# Main_Board.net
KiCad netlist of a schematic drawn in Altium Designer
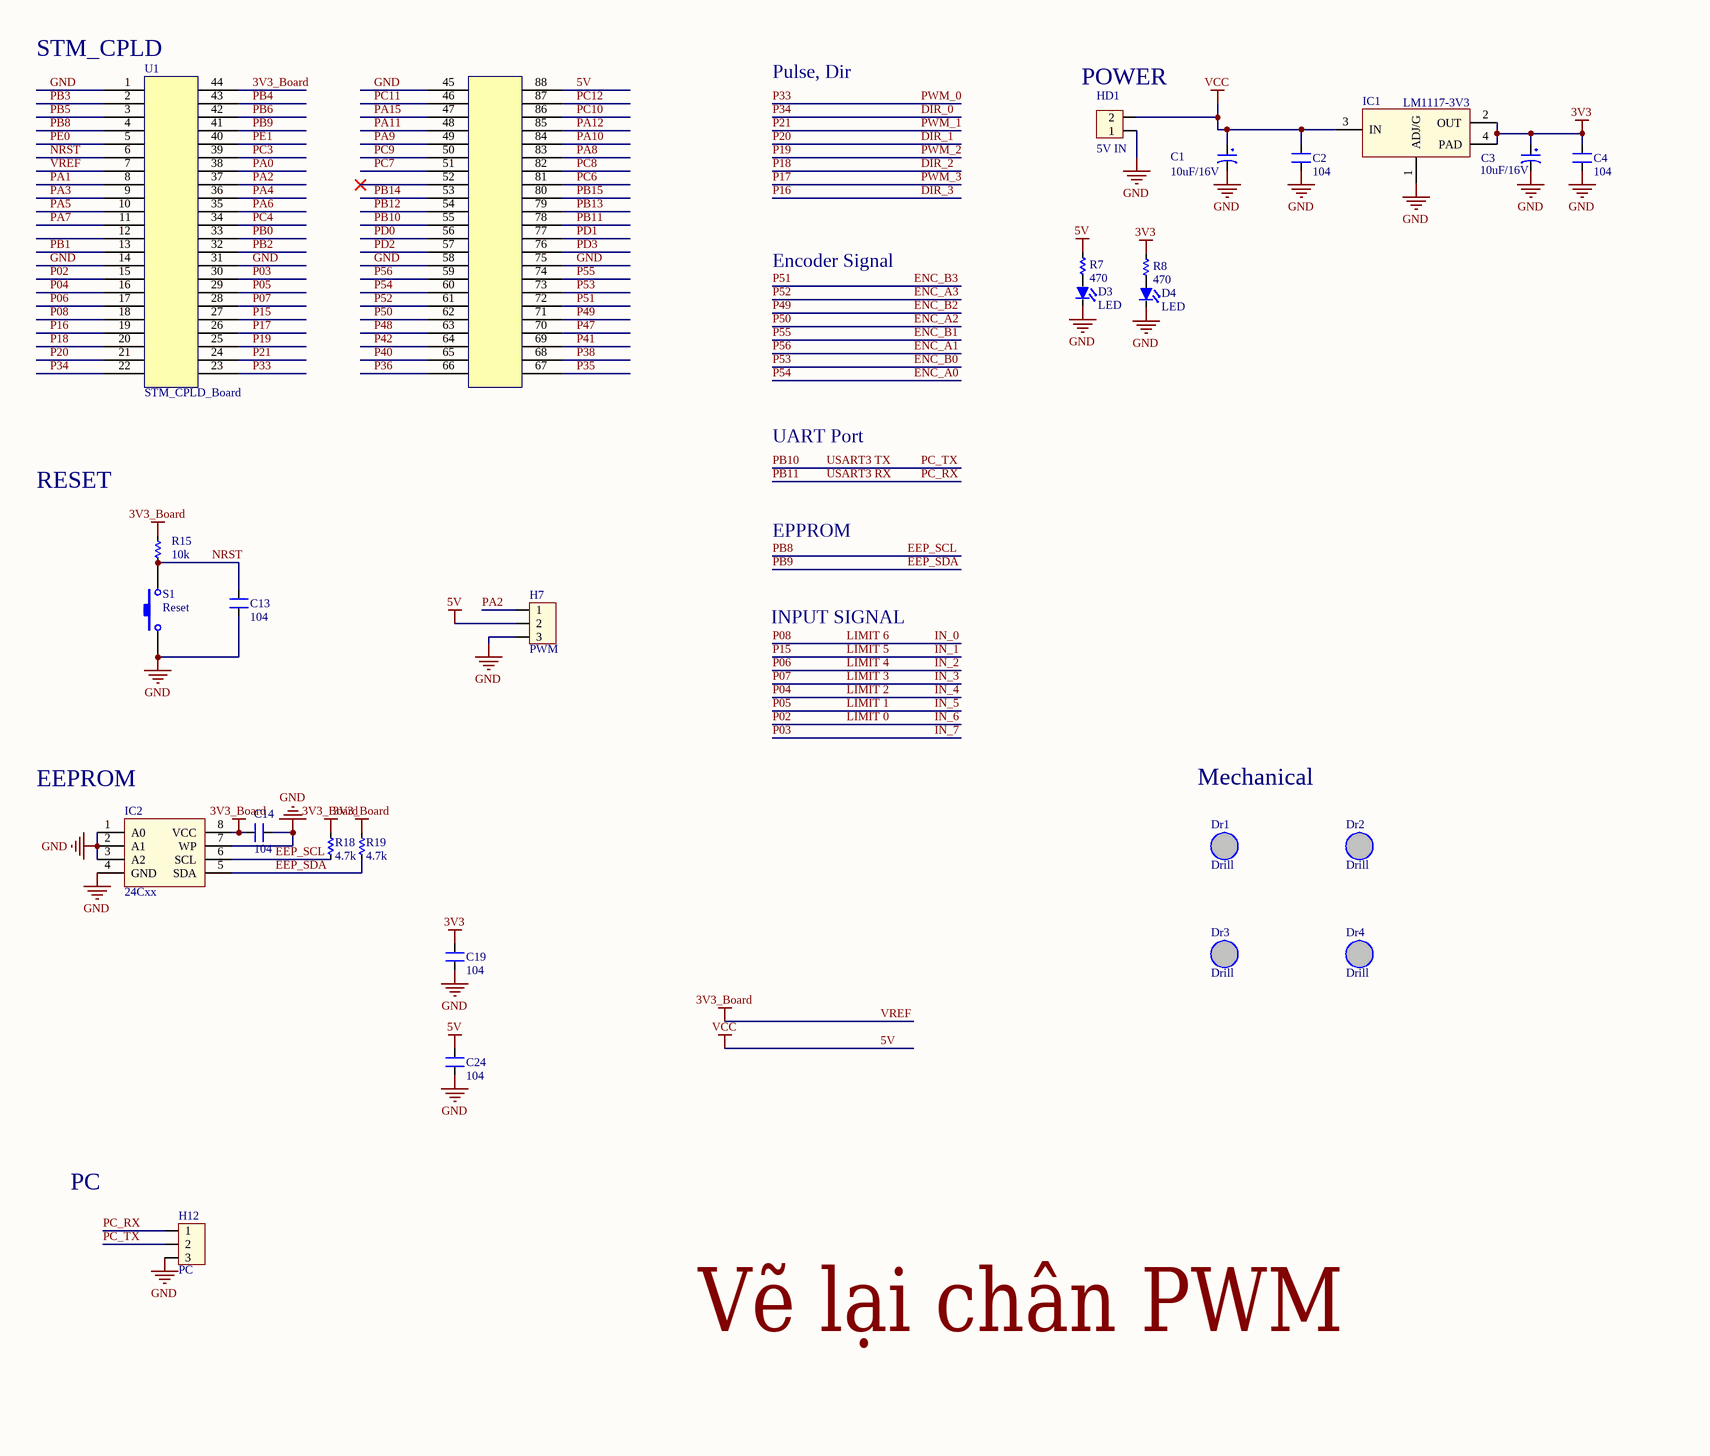
[diagram p0: Main_Board.SchDoc, top left]
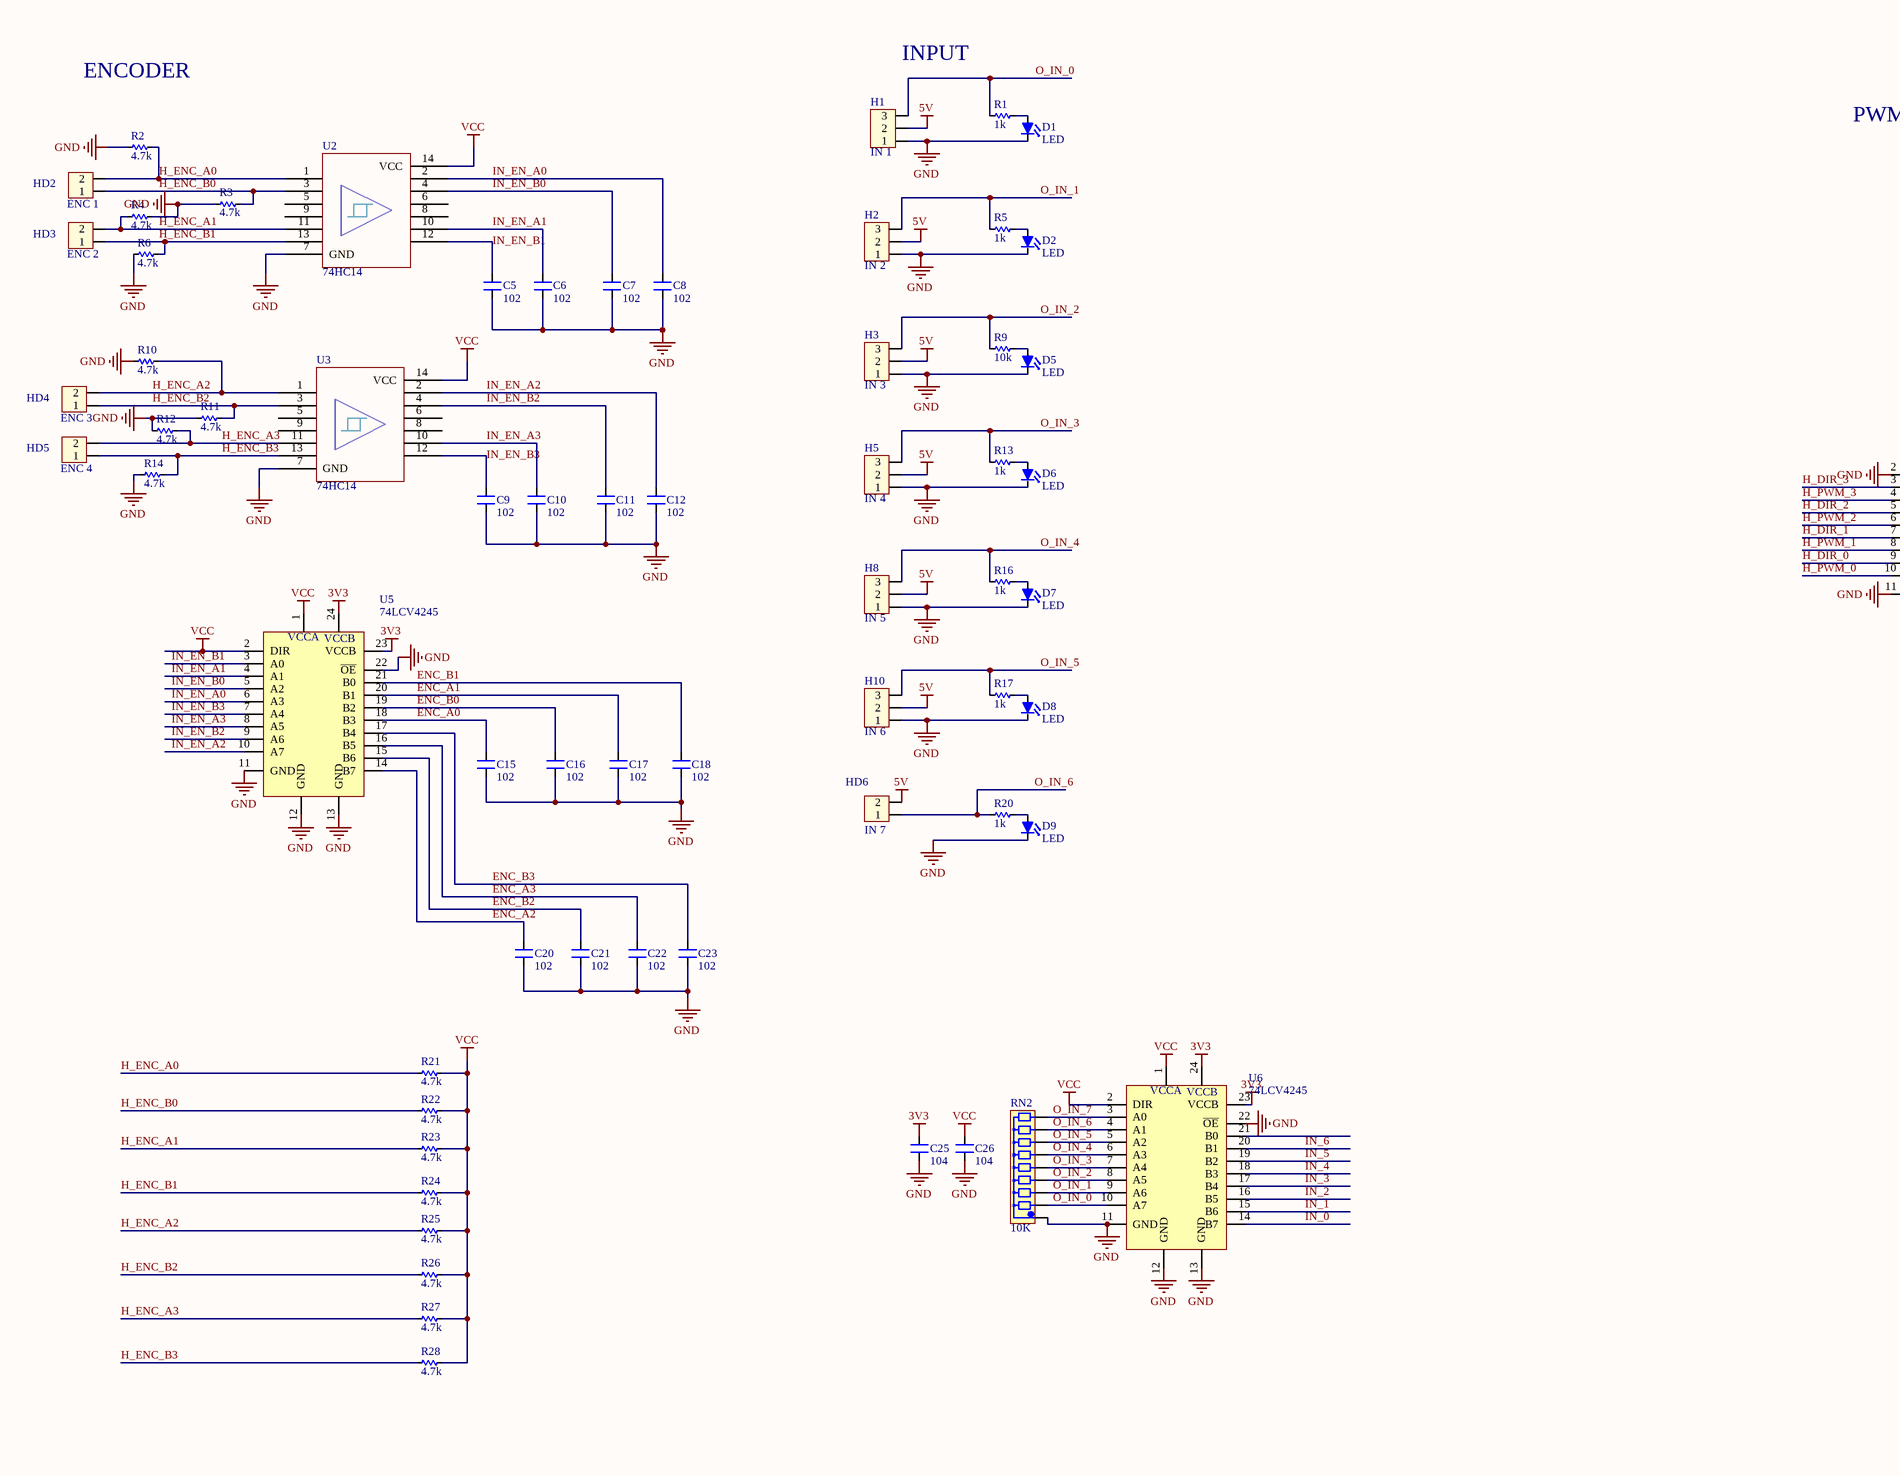
[diagram p1: Main_Board.SchDoc, top middle]
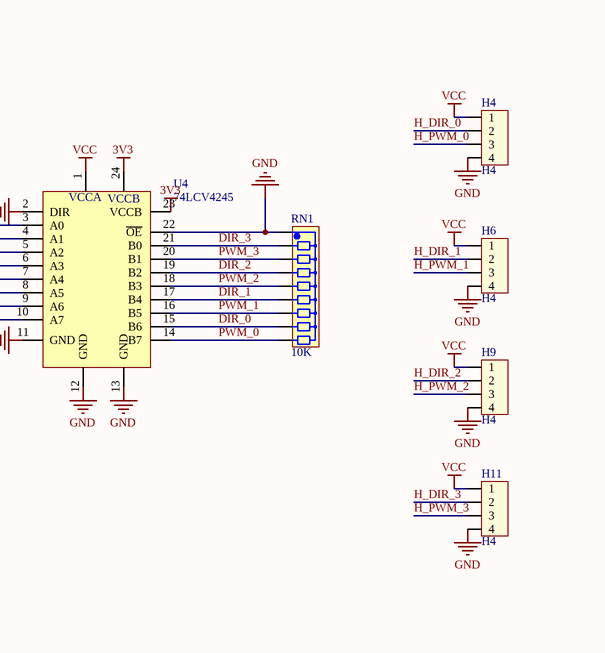
[diagram p2: Main_Board.SchDoc, top right]
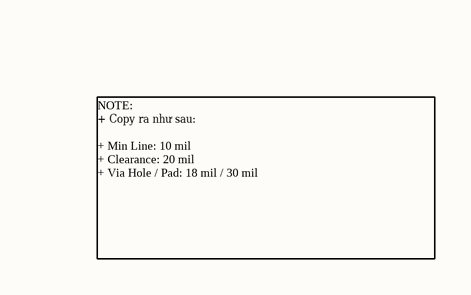
[diagram p3: Main_Board.SchDoc, bottom right]

(export (version "E")
  (design (tool "Eeschema 10.0.6"))
  (components
    (comp (ref "C1")
      (value "10uF/16V")
      (footprint "CAP_ALU_B")
      (description "C 47uF/50V , 220uF/16V")
      (libsource (lib "Main_Board") (part "CP2"))
    )
    (comp (ref "C2")
      (value "104")
      (footprint "CAP-SM-0805")
      (description "Ceramic Capacitor SMD")
      (libsource (lib "Main_Board") (part "CAP_SM_0805"))
    )
    (comp (ref "C3")
      (value "10uF/16V")
      (footprint "CAP_ALU_B")
      (description "C 47uF/50V , 220uF/16V")
      (libsource (lib "Main_Board") (part "CP2"))
    )
    (comp (ref "C4")
      (value "104")
      (footprint "CAP-SM-0805")
      (description "Ceramic Capacitor SMD")
      (libsource (lib "Main_Board") (part "CAP_SM_0805"))
    )
    (comp (ref "C5")
      (value "102")
      (footprint "CAP-SM-0805")
      (description "Ceramic Capacitor SMD")
      (libsource (lib "Main_Board") (part "CAP_SM_0805"))
    )
    (comp (ref "C6")
      (value "102")
      (footprint "CAP-SM-0805")
      (description "Ceramic Capacitor SMD")
      (libsource (lib "Main_Board") (part "CAP_SM_0805"))
    )
    (comp (ref "C7")
      (value "102")
      (footprint "CAP-SM-0805")
      (description "Ceramic Capacitor SMD")
      (libsource (lib "Main_Board") (part "CAP_SM_0805"))
    )
    (comp (ref "C8")
      (value "102")
      (footprint "CAP-SM-0805")
      (description "Ceramic Capacitor SMD")
      (libsource (lib "Main_Board") (part "CAP_SM_0805"))
    )
    (comp (ref "C9")
      (value "102")
      (footprint "CAP-SM-0805")
      (description "Ceramic Capacitor SMD")
      (libsource (lib "Main_Board") (part "CAP_SM_0805"))
    )
    (comp (ref "C10")
      (value "102")
      (footprint "CAP-SM-0805")
      (description "Ceramic Capacitor SMD")
      (libsource (lib "Main_Board") (part "CAP_SM_0805"))
    )
    (comp (ref "C11")
      (value "102")
      (footprint "CAP-SM-0805")
      (description "Ceramic Capacitor SMD")
      (libsource (lib "Main_Board") (part "CAP_SM_0805"))
    )
    (comp (ref "C12")
      (value "102")
      (footprint "CAP-SM-0805")
      (description "Ceramic Capacitor SMD")
      (libsource (lib "Main_Board") (part "CAP_SM_0805"))
    )
    (comp (ref "C13")
      (value "104")
      (footprint "CAP-SM-0805")
      (description "Ceramic Capacitor SMD")
      (libsource (lib "Main_Board") (part "CAP_SM_0805"))
    )
    (comp (ref "C14")
      (value "104")
      (footprint "CAP-SM-0805")
      (description "Ceramic Capacitor SMD")
      (libsource (lib "Main_Board") (part "CAP_SM_0805"))
    )
    (comp (ref "C15")
      (value "102")
      (footprint "CAP-SM-0805")
      (description "Ceramic Capacitor SMD")
      (libsource (lib "Main_Board") (part "CAP_SM_0805"))
    )
    (comp (ref "C16")
      (value "102")
      (footprint "CAP-SM-0805")
      (description "Ceramic Capacitor SMD")
      (libsource (lib "Main_Board") (part "CAP_SM_0805"))
    )
    (comp (ref "C17")
      (value "102")
      (footprint "CAP-SM-0805")
      (description "Ceramic Capacitor SMD")
      (libsource (lib "Main_Board") (part "CAP_SM_0805"))
    )
    (comp (ref "C18")
      (value "102")
      (footprint "CAP-SM-0805")
      (description "Ceramic Capacitor SMD")
      (libsource (lib "Main_Board") (part "CAP_SM_0805"))
    )
    (comp (ref "C19")
      (value "104")
      (footprint "CAP-SM-0805")
      (description "Ceramic Capacitor SMD")
      (libsource (lib "Main_Board") (part "CAP_SM_0805"))
    )
    (comp (ref "C20")
      (value "102")
      (footprint "CAP-SM-0805")
      (description "Ceramic Capacitor SMD")
      (libsource (lib "Main_Board") (part "CAP_SM_0805"))
    )
    (comp (ref "C21")
      (value "102")
      (footprint "CAP-SM-0805")
      (description "Ceramic Capacitor SMD")
      (libsource (lib "Main_Board") (part "CAP_SM_0805"))
    )
    (comp (ref "C22")
      (value "102")
      (footprint "CAP-SM-0805")
      (description "Ceramic Capacitor SMD")
      (libsource (lib "Main_Board") (part "CAP_SM_0805"))
    )
    (comp (ref "C23")
      (value "102")
      (footprint "CAP-SM-0805")
      (description "Ceramic Capacitor SMD")
      (libsource (lib "Main_Board") (part "CAP_SM_0805"))
    )
    (comp (ref "C24")
      (value "104")
      (footprint "CAP-SM-0805")
      (description "Ceramic Capacitor SMD")
      (libsource (lib "Main_Board") (part "CAP_SM_0805"))
    )
    (comp (ref "C25")
      (value "104")
      (footprint "CAP-SM-0805")
      (description "Ceramic Capacitor SMD")
      (libsource (lib "Main_Board") (part "CAP_SM_0805"))
    )
    (comp (ref "C26")
      (value "104")
      (footprint "CAP-SM-0805")
      (description "Ceramic Capacitor SMD")
      (libsource (lib "Main_Board") (part "CAP_SM_0805"))
    )
    (comp (ref "D1")
      (value "LED")
      (footprint "LED_0805_Blue")
      (description "LED SMD")
      (libsource (lib "Main_Board") (part "LED_SMD"))
    )
    (comp (ref "D2")
      (value "LED")
      (footprint "LED_0805_Blue")
      (description "LED SMD")
      (libsource (lib "Main_Board") (part "LED_SMD"))
    )
    (comp (ref "D3")
      (value "LED")
      (footprint "LED_0805_Blue")
      (description "LED SMD")
      (libsource (lib "Main_Board") (part "LED_SMD"))
    )
    (comp (ref "D4")
      (value "LED")
      (footprint "LED_0805_Blue")
      (description "LED SMD")
      (libsource (lib "Main_Board") (part "LED_SMD"))
    )
    (comp (ref "D5")
      (value "LED")
      (footprint "LED_0805_Blue")
      (description "LED SMD")
      (libsource (lib "Main_Board") (part "LED_SMD"))
    )
    (comp (ref "D6")
      (value "LED")
      (footprint "LED_0805_Blue")
      (description "LED SMD")
      (libsource (lib "Main_Board") (part "LED_SMD"))
    )
    (comp (ref "D7")
      (value "LED")
      (footprint "LED_0805_Blue")
      (description "LED SMD")
      (libsource (lib "Main_Board") (part "LED_SMD"))
    )
    (comp (ref "D8")
      (value "LED")
      (footprint "LED_0805_Blue")
      (description "LED SMD")
      (libsource (lib "Main_Board") (part "LED_SMD"))
    )
    (comp (ref "D9")
      (value "LED")
      (footprint "LED_0805_Blue")
      (description "LED SMD")
      (libsource (lib "Main_Board") (part "LED_SMD"))
    )
    (comp (ref "Dr1")
      (value "Drill")
      (footprint "Drill 3mm")
      (description "Drill 3mm")
      (libsource (lib "Main_Board") (part "Drill 3mm"))
    )
    (comp (ref "Dr2")
      (value "Drill")
      (footprint "Drill 3mm")
      (description "Drill 3mm")
      (libsource (lib "Main_Board") (part "Drill 3mm"))
    )
    (comp (ref "Dr3")
      (value "Drill")
      (footprint "Drill 3mm")
      (description "Drill 3mm")
      (libsource (lib "Main_Board") (part "Drill 3mm"))
    )
    (comp (ref "Dr4")
      (value "Drill")
      (footprint "Drill 3mm")
      (description "Drill 3mm")
      (libsource (lib "Main_Board") (part "Drill 3mm"))
    )
    (comp (ref "H1")
      (value "IN 1")
      (footprint "Header White 3")
      (description "Connector 3")
      (libsource (lib "") (part "Header white 3_1"))
    )
    (comp (ref "H2")
      (value "IN 2")
      (footprint "Header White 3")
      (description "Connector 3")
      (libsource (lib "") (part "Header white 3_1"))
    )
    (comp (ref "H3")
      (value "IN 3")
      (footprint "Header White 3")
      (description "Connector 3")
      (libsource (lib "") (part "Header white 3_1"))
    )
    (comp (ref "H4")
      (value "H4")
      (footprint "Header White 4")
      (description "Header white 4")
      (libsource (lib "Main_Board") (part "Header white 4"))
    )
    (comp (ref "H5")
      (value "IN 4")
      (footprint "Header White 3")
      (description "Connector 3")
      (libsource (lib "") (part "Header white 3_1"))
    )
    (comp (ref "H6")
      (value "H4")
      (footprint "Header White 4")
      (description "Header white 4")
      (libsource (lib "Main_Board") (part "Header white 4"))
    )
    (comp (ref "H7")
      (value "PWM")
      (footprint "Header White 3")
      (description "Connector 3")
      (libsource (lib "Main_Board") (part "Header white 3"))
    )
    (comp (ref "H8")
      (value "IN 5")
      (footprint "Header White 3")
      (description "Connector 3")
      (libsource (lib "") (part "Header white 3_1"))
    )
    (comp (ref "H9")
      (value "H4")
      (footprint "Header White 4")
      (description "Header white 4")
      (libsource (lib "Main_Board") (part "Header white 4"))
    )
    (comp (ref "H10")
      (value "IN 6")
      (footprint "Header White 3")
      (description "Connector 3")
      (libsource (lib "") (part "Header white 3_1"))
    )
    (comp (ref "H11")
      (value "H4")
      (footprint "Header White 4")
      (description "Header white 4")
      (libsource (lib "Main_Board") (part "Header white 4"))
    )
    (comp (ref "H12")
      (value "PC")
      (footprint "Header White 3")
      (description "Connector 3")
      (libsource (lib "Main_Board") (part "Header white 3"))
    )
    (comp (ref "HD1")
      (value "5V IN")
      (footprint "Domino 2")
      (description "Domino 2 200mil")
      (libsource (lib "Main_Board") (part "Domino 2"))
    )
    (comp (ref "HD2")
      (value "ENC 1")
      (footprint "Domino 2")
      (description "Domino 2 200mil")
      (libsource (lib "Main_Board") (part "Domino 2"))
    )
    (comp (ref "HD3")
      (value "ENC 2")
      (footprint "Domino 2")
      (description "Domino 2 200mil")
      (libsource (lib "Main_Board") (part "Domino 2"))
    )
    (comp (ref "HD4")
      (value "ENC 3")
      (footprint "Domino 2")
      (description "Domino 2 200mil")
      (libsource (lib "Main_Board") (part "Domino 2"))
    )
    (comp (ref "HD5")
      (value "ENC 4")
      (footprint "Domino 2")
      (description "Domino 2 200mil")
      (libsource (lib "Main_Board") (part "Domino 2"))
    )
    (comp (ref "HD6")
      (value "IN 7")
      (footprint "Domino 2")
      (description "Domino 2 200mil")
      (libsource (lib "Main_Board") (part "Domino 2"))
    )
    (comp (ref "IC1")
      (value "LM1117-3V3")
      (footprint "SOT223-4N")
      (description "Available in 1.8V, 2.5V, 2.85V, 3.3V, 5V, and  Adjustable Versions")
      (libsource (lib "Main_Board") (part "LM1117"))
    )
    (comp (ref "IC2")
      (value "24Cxx")
      (footprint "SOIC8")
      (description "Standard 2-Wire Bus Interface Serial EEPROM")
      (fields (field (name "COPYRIGHT BY") "VanDungEvn"))
      (libsource (lib "Main_Board") (part "24Cxx"))
    )
    (comp (ref "R1")
      (value "1k")
      (footprint "RES-SM-0805")
      (description "Resistor")
      (fields
        (field (name "MANUFACTURER") "Generic Components")
        (field (name "PUBLISHER") "Altium Hobart Technology Centre")
      )
      (libsource (lib "Main_Board") (part "Res-SMD"))
    )
    (comp (ref "R2")
      (value "4.7k")
      (footprint "RES-SM-0805")
      (description "Resistor")
      (fields
        (field (name "MANUFACTURER") "Generic Components")
        (field (name "PUBLISHER") "Altium Hobart Technology Centre")
      )
      (libsource (lib "Main_Board") (part "Res-SMD"))
    )
    (comp (ref "R3")
      (value "4.7k")
      (footprint "RES-SM-0805")
      (description "Resistor")
      (fields
        (field (name "MANUFACTURER") "Generic Components")
        (field (name "PUBLISHER") "Altium Hobart Technology Centre")
      )
      (libsource (lib "Main_Board") (part "Res-SMD"))
    )
    (comp (ref "R4")
      (value "4.7k")
      (footprint "RES-SM-0805")
      (description "Resistor")
      (fields
        (field (name "MANUFACTURER") "Generic Components")
        (field (name "PUBLISHER") "Altium Hobart Technology Centre")
      )
      (libsource (lib "Main_Board") (part "Res-SMD"))
    )
    (comp (ref "R5")
      (value "1k")
      (footprint "RES-SM-0805")
      (description "Resistor")
      (fields
        (field (name "MANUFACTURER") "Generic Components")
        (field (name "PUBLISHER") "Altium Hobart Technology Centre")
      )
      (libsource (lib "Main_Board") (part "Res-SMD"))
    )
    (comp (ref "R6")
      (value "4.7k")
      (footprint "RES-SM-0805")
      (description "Resistor")
      (fields
        (field (name "MANUFACTURER") "Generic Components")
        (field (name "PUBLISHER") "Altium Hobart Technology Centre")
      )
      (libsource (lib "Main_Board") (part "Res-SMD"))
    )
    (comp (ref "R7")
      (value "470")
      (footprint "RES-SM-0805")
      (description "Resistor")
      (fields
        (field (name "MANUFACTURER") "Generic Components")
        (field (name "PUBLISHER") "Altium Hobart Technology Centre")
      )
      (libsource (lib "Main_Board") (part "Res-SMD"))
    )
    (comp (ref "R8")
      (value "470")
      (footprint "RES-SM-0805")
      (description "Resistor")
      (fields
        (field (name "MANUFACTURER") "Generic Components")
        (field (name "PUBLISHER") "Altium Hobart Technology Centre")
      )
      (libsource (lib "Main_Board") (part "Res-SMD"))
    )
    (comp (ref "R9")
      (value "10k")
      (footprint "RES-SM-0805")
      (description "Resistor")
      (fields
        (field (name "MANUFACTURER") "Generic Components")
        (field (name "PUBLISHER") "Altium Hobart Technology Centre")
      )
      (libsource (lib "Main_Board") (part "Res-SMD"))
    )
    (comp (ref "R10")
      (value "4.7k")
      (footprint "RES-SM-0805")
      (description "Resistor")
      (fields
        (field (name "MANUFACTURER") "Generic Components")
        (field (name "PUBLISHER") "Altium Hobart Technology Centre")
      )
      (libsource (lib "Main_Board") (part "Res-SMD"))
    )
    (comp (ref "R11")
      (value "4.7k")
      (footprint "RES-SM-0805")
      (description "Resistor")
      (fields
        (field (name "MANUFACTURER") "Generic Components")
        (field (name "PUBLISHER") "Altium Hobart Technology Centre")
      )
      (libsource (lib "Main_Board") (part "Res-SMD"))
    )
    (comp (ref "R12")
      (value "4.7k")
      (footprint "RES-SM-0805")
      (description "Resistor")
      (fields
        (field (name "MANUFACTURER") "Generic Components")
        (field (name "PUBLISHER") "Altium Hobart Technology Centre")
      )
      (libsource (lib "Main_Board") (part "Res-SMD"))
    )
    (comp (ref "R13")
      (value "1k")
      (footprint "RES-SM-0805")
      (description "Resistor")
      (fields
        (field (name "MANUFACTURER") "Generic Components")
        (field (name "PUBLISHER") "Altium Hobart Technology Centre")
      )
      (libsource (lib "Main_Board") (part "Res-SMD"))
    )
    (comp (ref "R14")
      (value "4.7k")
      (footprint "RES-SM-0805")
      (description "Resistor")
      (fields
        (field (name "MANUFACTURER") "Generic Components")
        (field (name "PUBLISHER") "Altium Hobart Technology Centre")
      )
      (libsource (lib "Main_Board") (part "Res-SMD"))
    )
    (comp (ref "R15")
      (value "10k")
      (footprint "RES-SM-0805")
      (description "Resistor")
      (fields
        (field (name "MANUFACTURER") "Generic Components")
        (field (name "PUBLISHER") "Altium Hobart Technology Centre")
      )
      (libsource (lib "Main_Board") (part "Res-SMD"))
    )
    (comp (ref "R16")
      (value "1k")
      (footprint "RES-SM-0805")
      (description "Resistor")
      (fields
        (field (name "MANUFACTURER") "Generic Components")
        (field (name "PUBLISHER") "Altium Hobart Technology Centre")
      )
      (libsource (lib "Main_Board") (part "Res-SMD"))
    )
    (comp (ref "R17")
      (value "1k")
      (footprint "RES-SM-0805")
      (description "Resistor")
      (fields
        (field (name "MANUFACTURER") "Generic Components")
        (field (name "PUBLISHER") "Altium Hobart Technology Centre")
      )
      (libsource (lib "Main_Board") (part "Res-SMD"))
    )
    (comp (ref "R18")
      (value "4.7k")
      (footprint "RES-SM-0805")
      (description "Resistor")
      (fields
        (field (name "MANUFACTURER") "Generic Components")
        (field (name "PUBLISHER") "Altium Hobart Technology Centre")
      )
      (libsource (lib "Main_Board") (part "Res-SMD"))
    )
    (comp (ref "R19")
      (value "4.7k")
      (footprint "RES-SM-0805")
      (description "Resistor")
      (fields
        (field (name "MANUFACTURER") "Generic Components")
        (field (name "PUBLISHER") "Altium Hobart Technology Centre")
      )
      (libsource (lib "Main_Board") (part "Res-SMD"))
    )
    (comp (ref "R20")
      (value "1k")
      (footprint "RES-SM-0805")
      (description "Resistor")
      (fields
        (field (name "MANUFACTURER") "Generic Components")
        (field (name "PUBLISHER") "Altium Hobart Technology Centre")
      )
      (libsource (lib "Main_Board") (part "Res-SMD"))
    )
    (comp (ref "R21")
      (value "4.7k")
      (footprint "RES-SM-0805")
      (description "Resistor")
      (fields
        (field (name "MANUFACTURER") "Generic Components")
        (field (name "PUBLISHER") "Altium Hobart Technology Centre")
      )
      (libsource (lib "Main_Board") (part "Res-SMD"))
    )
    (comp (ref "R22")
      (value "4.7k")
      (footprint "RES-SM-0805")
      (description "Resistor")
      (fields
        (field (name "MANUFACTURER") "Generic Components")
        (field (name "PUBLISHER") "Altium Hobart Technology Centre")
      )
      (libsource (lib "Main_Board") (part "Res-SMD"))
    )
    (comp (ref "R23")
      (value "4.7k")
      (footprint "RES-SM-0805")
      (description "Resistor")
      (fields
        (field (name "MANUFACTURER") "Generic Components")
        (field (name "PUBLISHER") "Altium Hobart Technology Centre")
      )
      (libsource (lib "Main_Board") (part "Res-SMD"))
    )
    (comp (ref "R24")
      (value "4.7k")
      (footprint "RES-SM-0805")
      (description "Resistor")
      (fields
        (field (name "MANUFACTURER") "Generic Components")
        (field (name "PUBLISHER") "Altium Hobart Technology Centre")
      )
      (libsource (lib "Main_Board") (part "Res-SMD"))
    )
    (comp (ref "R25")
      (value "4.7k")
      (footprint "RES-SM-0805")
      (description "Resistor")
      (fields
        (field (name "MANUFACTURER") "Generic Components")
        (field (name "PUBLISHER") "Altium Hobart Technology Centre")
      )
      (libsource (lib "Main_Board") (part "Res-SMD"))
    )
    (comp (ref "R26")
      (value "4.7k")
      (footprint "RES-SM-0805")
      (description "Resistor")
      (fields
        (field (name "MANUFACTURER") "Generic Components")
        (field (name "PUBLISHER") "Altium Hobart Technology Centre")
      )
      (libsource (lib "Main_Board") (part "Res-SMD"))
    )
    (comp (ref "R27")
      (value "4.7k")
      (footprint "RES-SM-0805")
      (description "Resistor")
      (fields
        (field (name "MANUFACTURER") "Generic Components")
        (field (name "PUBLISHER") "Altium Hobart Technology Centre")
      )
      (libsource (lib "Main_Board") (part "Res-SMD"))
    )
    (comp (ref "R28")
      (value "4.7k")
      (footprint "RES-SM-0805")
      (description "Resistor")
      (fields
        (field (name "MANUFACTURER") "Generic Components")
        (field (name "PUBLISHER") "Altium Hobart Technology Centre")
      )
      (libsource (lib "Main_Board") (part "Res-SMD"))
    )
    (comp (ref "RN1")
      (value "10K")
      (footprint "RN8")
      (description "Resistor 8 (Thanh)")
      (libsource (lib "") (part "RN8_1"))
    )
    (comp (ref "RN2")
      (value "10K")
      (footprint "RN8")
      (description "Resistor 8 (Thanh)")
      (libsource (lib "Main_Board") (part "RN8"))
    )
    (comp (ref "S1")
      (value "Reset")
      (footprint "SW2")
      (description "Switch button 2 pin")
      (libsource (lib "Main_Board") (part "SW - 2Pin"))
    )
    (comp (ref "U1")
      (value "STM_CPLD_Board")
      (footprint "STM_CPLD_Board")
      (description "STM32f4 and Max2 570 on one board")
      (libsource (lib "Main_Board") (part "STM_CPLD_Board"))
    )
    (comp (ref "U2")
      (value "74HC14")
      (footprint "SO14-150mil")
      (description "Hex Inverters With SCHMITT-TRIGGER Inputs")
      (libsource (lib "Main_Board") (part "74HC14"))
    )
    (comp (ref "U3")
      (value "74HC14")
      (footprint "SO14-150mil")
      (description "Hex Inverters With SCHMITT-TRIGGER Inputs")
      (libsource (lib "Main_Board") (part "74HC14"))
    )
    (comp (ref "U4")
      (value "74LCV4245")
      (footprint "SOIC24 - wide")
      (description "Octal dual supply translating transceiver; 3-state")
      (libsource (lib "Main_Board") (part "74LCV4245"))
    )
    (comp (ref "U5")
      (value "74LCV4245")
      (footprint "SOIC24 - wide")
      (description "Octal dual supply translating transceiver; 3-state")
      (libsource (lib "Main_Board") (part "74LCV4245"))
    )
    (comp (ref "U6")
      (value "74LCV4245")
      (footprint "SOIC24 - wide")
      (description "Octal dual supply translating transceiver; 3-state")
      (libsource (lib "Main_Board") (part "74LCV4245"))
    )
  )
  (nets
    (net (code "1") (name "/DIR_0") (class "Default")
      (node (ref "RN1") (pin "8") (pinfunction "8_8") (pintype "passive"))
      (node (ref "U1") (pin "22") (pinfunction "22_22") (pintype "passive"))
      (node (ref "U4") (pin "15") (pinfunction "B6_15") (pintype "passive"))
    )
    (net (code "2") (name "/DIR_1") (class "Default")
      (node (ref "RN1") (pin "6") (pinfunction "6_6") (pintype "passive"))
      (node (ref "U1") (pin "21") (pinfunction "21_21") (pintype "passive"))
      (node (ref "U4") (pin "17") (pinfunction "B4_17") (pintype "passive"))
    )
    (net (code "3") (name "/DIR_2") (class "Default")
      (node (ref "RN1") (pin "4") (pinfunction "4_4") (pintype "passive"))
      (node (ref "U1") (pin "20") (pinfunction "20_20") (pintype "passive"))
      (node (ref "U4") (pin "19") (pinfunction "B2_19") (pintype "passive"))
    )
    (net (code "4") (name "/DIR_3") (class "Default")
      (node (ref "RN1") (pin "2") (pinfunction "2_2") (pintype "passive"))
      (node (ref "U1") (pin "19") (pinfunction "19_19") (pintype "passive"))
      (node (ref "U4") (pin "21") (pinfunction "B0_21") (pintype "passive"))
    )
    (net (code "5") (name "/EEP_SCL") (class "Default")
      (node (ref "IC2") (pin "6") (pinfunction "SCL_6") (pintype "passive"))
      (node (ref "R18") (pin "1") (pinfunction "1_1") (pintype "passive"))
      (node (ref "U1") (pin "4") (pinfunction "4_4") (pintype "passive"))
    )
    (net (code "6") (name "/EEP_SDA") (class "Default")
      (node (ref "IC2") (pin "5") (pinfunction "SDA_5") (pintype "passive"))
      (node (ref "R19") (pin "2") (pinfunction "2_2") (pintype "passive"))
      (node (ref "U1") (pin "41") (pinfunction "41_41") (pintype "passive"))
    )
    (net (code "7") (name "/ENC_A0") (class "Default")
      (node (ref "C15") (pin "2") (pinfunction "2_2") (pintype "passive"))
      (node (ref "U1") (pin "60") (pinfunction "60_60") (pintype "passive"))
      (node (ref "U5") (pin "18") (pinfunction "B3_18") (pintype "passive"))
    )
    (net (code "8") (name "/ENC_A1") (class "Default")
      (node (ref "C17") (pin "2") (pinfunction "2_2") (pintype "passive"))
      (node (ref "U1") (pin "59") (pinfunction "59_59") (pintype "passive"))
      (node (ref "U5") (pin "20") (pinfunction "B1_20") (pintype "passive"))
    )
    (net (code "9") (name "/ENC_A2") (class "Default")
      (node (ref "C20") (pin "2") (pinfunction "2_2") (pintype "passive"))
      (node (ref "U1") (pin "62") (pinfunction "62_62") (pintype "passive"))
      (node (ref "U5") (pin "14") (pinfunction "B7_14") (pintype "passive"))
    )
    (net (code "10") (name "/ENC_A3") (class "Default")
      (node (ref "C22") (pin "2") (pinfunction "2_2") (pintype "passive"))
      (node (ref "U1") (pin "61") (pinfunction "61_61") (pintype "passive"))
      (node (ref "U5") (pin "16") (pinfunction "B5_16") (pintype "passive"))
    )
    (net (code "11") (name "/ENC_B0") (class "Default")
      (node (ref "C16") (pin "2") (pinfunction "2_2") (pintype "passive"))
      (node (ref "U1") (pin "73") (pinfunction "73_73") (pintype "passive"))
      (node (ref "U5") (pin "19") (pinfunction "B2_19") (pintype "passive"))
    )
    (net (code "12") (name "/ENC_B1") (class "Default")
      (node (ref "C18") (pin "2") (pinfunction "2_2") (pintype "passive"))
      (node (ref "U1") (pin "74") (pinfunction "74_74") (pintype "passive"))
      (node (ref "U5") (pin "21") (pinfunction "B0_21") (pintype "passive"))
    )
    (net (code "13") (name "/ENC_B2") (class "Default")
      (node (ref "C21") (pin "2") (pinfunction "2_2") (pintype "passive"))
      (node (ref "U1") (pin "71") (pinfunction "71_71") (pintype "passive"))
      (node (ref "U5") (pin "15") (pinfunction "B6_15") (pintype "passive"))
    )
    (net (code "14") (name "/ENC_B3") (class "Default")
      (node (ref "C23") (pin "2") (pinfunction "2_2") (pintype "passive"))
      (node (ref "U1") (pin "72") (pinfunction "72_72") (pintype "passive"))
      (node (ref "U5") (pin "17") (pinfunction "B4_17") (pintype "passive"))
    )
    (net (code "15") (name "/H_DIR_0") (class "Default")
      (node (ref "H4") (pin "2") (pinfunction "2_2") (pintype "passive"))
      (node (ref "U4") (pin "9") (pinfunction "A6_9") (pintype "passive"))
    )
    (net (code "16") (name "/H_DIR_1") (class "Default")
      (node (ref "H6") (pin "2") (pinfunction "2_2") (pintype "passive"))
      (node (ref "U4") (pin "7") (pinfunction "A4_7") (pintype "passive"))
    )
    (net (code "17") (name "/H_DIR_2") (class "Default")
      (node (ref "H9") (pin "2") (pinfunction "2_2") (pintype "passive"))
      (node (ref "U4") (pin "5") (pinfunction "A2_5") (pintype "passive"))
    )
    (net (code "18") (name "/H_DIR_3") (class "Default")
      (node (ref "H11") (pin "2") (pinfunction "2_2") (pintype "passive"))
      (node (ref "U4") (pin "3") (pinfunction "A0_3") (pintype "passive"))
    )
    (net (code "19") (name "/H_ENC_A0") (class "Default")
      (node (ref "HD2") (pin "2") (pinfunction "2_2") (pintype "passive"))
      (node (ref "R2") (pin "1") (pinfunction "1_1") (pintype "passive"))
      (node (ref "R21") (pin "1") (pinfunction "1_1") (pintype "passive"))
      (node (ref "U2") (pin "1") (pintype "passive"))
    )
    (net (code "20") (name "/H_ENC_A1") (class "Default")
      (node (ref "HD3") (pin "2") (pinfunction "2_2") (pintype "passive"))
      (node (ref "R23") (pin "1") (pinfunction "1_1") (pintype "passive"))
      (node (ref "R4") (pin "2") (pinfunction "2_2") (pintype "passive"))
      (node (ref "U2") (pin "11") (pinfunction "10_11") (pintype "passive"))
    )
    (net (code "21") (name "/H_ENC_A2") (class "Default")
      (node (ref "HD4") (pin "2") (pinfunction "2_2") (pintype "passive"))
      (node (ref "R10") (pin "1") (pinfunction "1_1") (pintype "passive"))
      (node (ref "R25") (pin "1") (pinfunction "1_1") (pintype "passive"))
      (node (ref "U3") (pin "1") (pintype "passive"))
    )
    (net (code "22") (name "/H_ENC_A3") (class "Default")
      (node (ref "HD5") (pin "2") (pinfunction "2_2") (pintype "passive"))
      (node (ref "R12") (pin "1") (pinfunction "1_1") (pintype "passive"))
      (node (ref "R27") (pin "1") (pinfunction "1_1") (pintype "passive"))
      (node (ref "U3") (pin "11") (pinfunction "10_11") (pintype "passive"))
    )
    (net (code "23") (name "/H_ENC_B0") (class "Default")
      (node (ref "HD2") (pin "1") (pinfunction "1_1") (pintype "passive"))
      (node (ref "R22") (pin "1") (pinfunction "1_1") (pintype "passive"))
      (node (ref "R3") (pin "1") (pinfunction "1_1") (pintype "passive"))
      (node (ref "U2") (pin "3") (pintype "passive"))
    )
    (net (code "24") (name "/H_ENC_B1") (class "Default")
      (node (ref "HD3") (pin "1") (pinfunction "1_1") (pintype "passive"))
      (node (ref "R24") (pin "1") (pinfunction "1_1") (pintype "passive"))
      (node (ref "R6") (pin "1") (pinfunction "1_1") (pintype "passive"))
      (node (ref "U2") (pin "13") (pinfunction "12_13") (pintype "passive"))
    )
    (net (code "25") (name "/H_ENC_B2") (class "Default")
      (node (ref "HD4") (pin "1") (pinfunction "1_1") (pintype "passive"))
      (node (ref "R11") (pin "1") (pinfunction "1_1") (pintype "passive"))
      (node (ref "R26") (pin "1") (pinfunction "1_1") (pintype "passive"))
      (node (ref "U3") (pin "3") (pintype "passive"))
    )
    (net (code "26") (name "/H_ENC_B3") (class "Default")
      (node (ref "HD5") (pin "1") (pinfunction "1_1") (pintype "passive"))
      (node (ref "R14") (pin "1") (pinfunction "1_1") (pintype "passive"))
      (node (ref "R28") (pin "1") (pinfunction "1_1") (pintype "passive"))
      (node (ref "U3") (pin "13") (pinfunction "12_13") (pintype "passive"))
    )
    (net (code "27") (name "/H_PWM_0") (class "Default")
      (node (ref "H4") (pin "3") (pinfunction "3_3") (pintype "passive"))
      (node (ref "U4") (pin "10") (pinfunction "A7_10") (pintype "passive"))
    )
    (net (code "28") (name "/H_PWM_1") (class "Default")
      (node (ref "H6") (pin "3") (pinfunction "3_3") (pintype "passive"))
      (node (ref "U4") (pin "8") (pinfunction "A5_8") (pintype "passive"))
    )
    (net (code "29") (name "/H_PWM_2") (class "Default")
      (node (ref "H9") (pin "3") (pinfunction "3_3") (pintype "passive"))
      (node (ref "U4") (pin "6") (pinfunction "A3_6") (pintype "passive"))
    )
    (net (code "30") (name "/H_PWM_3") (class "Default")
      (node (ref "H11") (pin "3") (pinfunction "3_3") (pintype "passive"))
      (node (ref "U4") (pin "4") (pinfunction "A1_4") (pintype "passive"))
    )
    (net (code "31") (name "/IN_0") (class "Default")
      (node (ref "U1") (pin "18") (pinfunction "18_18") (pintype "passive"))
      (node (ref "U6") (pin "14") (pinfunction "B7_14") (pintype "passive"))
    )
    (net (code "32") (name "/IN_1") (class "Default")
      (node (ref "U1") (pin "27") (pinfunction "27_27") (pintype "passive"))
      (node (ref "U6") (pin "15") (pinfunction "B6_15") (pintype "passive"))
    )
    (net (code "33") (name "/IN_2") (class "Default")
      (node (ref "U1") (pin "17") (pinfunction "17_17") (pintype "passive"))
      (node (ref "U6") (pin "16") (pinfunction "B5_16") (pintype "passive"))
    )
    (net (code "34") (name "/IN_3") (class "Default")
      (node (ref "U1") (pin "28") (pinfunction "28_28") (pintype "passive"))
      (node (ref "U6") (pin "17") (pinfunction "B4_17") (pintype "passive"))
    )
    (net (code "35") (name "/IN_4") (class "Default")
      (node (ref "U1") (pin "16") (pinfunction "16_16") (pintype "passive"))
      (node (ref "U6") (pin "18") (pinfunction "B3_18") (pintype "passive"))
    )
    (net (code "36") (name "/IN_5") (class "Default")
      (node (ref "U1") (pin "29") (pinfunction "29_29") (pintype "passive"))
      (node (ref "U6") (pin "19") (pinfunction "B2_19") (pintype "passive"))
    )
    (net (code "37") (name "/IN_6") (class "Default")
      (node (ref "U1") (pin "15") (pinfunction "15_15") (pintype "passive"))
      (node (ref "U6") (pin "20") (pinfunction "B1_20") (pintype "passive"))
    )
    (net (code "38") (name "/IN_7") (class "Default")
      (node (ref "U1") (pin "30") (pinfunction "30_30") (pintype "passive"))
    )
    (net (code "39") (name "/IN_EN_A0") (class "Default")
      (node (ref "C8") (pin "2") (pinfunction "2_2") (pintype "passive"))
      (node (ref "U2") (pin "2") (pintype "passive"))
      (node (ref "U5") (pin "6") (pinfunction "A3_6") (pintype "passive"))
    )
    (net (code "40") (name "/IN_EN_A1") (class "Default")
      (node (ref "C6") (pin "2") (pinfunction "2_2") (pintype "passive"))
      (node (ref "U2") (pin "10") (pinfunction "9_10") (pintype "passive"))
      (node (ref "U5") (pin "4") (pinfunction "A1_4") (pintype "passive"))
    )
    (net (code "41") (name "/IN_EN_A2") (class "Default")
      (node (ref "C12") (pin "2") (pinfunction "2_2") (pintype "passive"))
      (node (ref "U3") (pin "2") (pintype "passive"))
      (node (ref "U5") (pin "10") (pinfunction "A7_10") (pintype "passive"))
    )
    (net (code "42") (name "/IN_EN_A3") (class "Default")
      (node (ref "C10") (pin "2") (pinfunction "2_2") (pintype "passive"))
      (node (ref "U3") (pin "10") (pinfunction "9_10") (pintype "passive"))
      (node (ref "U5") (pin "8") (pinfunction "A5_8") (pintype "passive"))
    )
    (net (code "43") (name "/IN_EN_B0") (class "Default")
      (node (ref "C7") (pin "2") (pinfunction "2_2") (pintype "passive"))
      (node (ref "U2") (pin "4") (pintype "passive"))
      (node (ref "U5") (pin "5") (pinfunction "A2_5") (pintype "passive"))
    )
    (net (code "44") (name "/IN_EN_B1") (class "Default")
      (node (ref "C5") (pin "2") (pinfunction "2_2") (pintype "passive"))
      (node (ref "U2") (pin "12") (pinfunction "11_12") (pintype "passive"))
      (node (ref "U5") (pin "3") (pinfunction "A0_3") (pintype "passive"))
    )
    (net (code "45") (name "/IN_EN_B2") (class "Default")
      (node (ref "C11") (pin "2") (pinfunction "2_2") (pintype "passive"))
      (node (ref "U3") (pin "4") (pintype "passive"))
      (node (ref "U5") (pin "9") (pinfunction "A6_9") (pintype "passive"))
    )
    (net (code "46") (name "/IN_EN_B3") (class "Default")
      (node (ref "C9") (pin "2") (pinfunction "2_2") (pintype "passive"))
      (node (ref "U3") (pin "12") (pinfunction "11_12") (pintype "passive"))
      (node (ref "U5") (pin "7") (pinfunction "A4_7") (pintype "passive"))
    )
    (net (code "47") (name "/NRST") (class "Default")
      (node (ref "C13") (pin "1") (pinfunction "1_1") (pintype "passive"))
      (node (ref "R15") (pin "2") (pinfunction "2_2") (pintype "passive"))
      (node (ref "S1") (pin "2") (pinfunction "2_2") (pintype "passive"))
      (node (ref "U1") (pin "6") (pinfunction "6_6") (pintype "passive"))
    )
    (net (code "48") (name "/O_IN_0") (class "Default")
      (node (ref "H1") (pin "3") (pinfunction "3_3") (pintype "passive"))
      (node (ref "R1") (pin "2") (pinfunction "2_2") (pintype "passive"))
      (node (ref "RN2") (pin "2") (pinfunction "2_2") (pintype "passive"))
      (node (ref "U6") (pin "10") (pinfunction "A7_10") (pintype "passive"))
    )
    (net (code "49") (name "/O_IN_1") (class "Default")
      (node (ref "H2") (pin "3") (pinfunction "3_3") (pintype "passive"))
      (node (ref "R5") (pin "2") (pinfunction "2_2") (pintype "passive"))
      (node (ref "RN2") (pin "3") (pinfunction "3_3") (pintype "passive"))
      (node (ref "U6") (pin "9") (pinfunction "A6_9") (pintype "passive"))
    )
    (net (code "50") (name "/O_IN_2") (class "Default")
      (node (ref "H3") (pin "3") (pinfunction "3_3") (pintype "passive"))
      (node (ref "R9") (pin "2") (pinfunction "2_2") (pintype "passive"))
      (node (ref "RN2") (pin "4") (pinfunction "4_4") (pintype "passive"))
      (node (ref "U6") (pin "8") (pinfunction "A5_8") (pintype "passive"))
    )
    (net (code "51") (name "/O_IN_3") (class "Default")
      (node (ref "H5") (pin "3") (pinfunction "3_3") (pintype "passive"))
      (node (ref "R13") (pin "2") (pinfunction "2_2") (pintype "passive"))
      (node (ref "RN2") (pin "5") (pinfunction "5_5") (pintype "passive"))
      (node (ref "U6") (pin "7") (pinfunction "A4_7") (pintype "passive"))
    )
    (net (code "52") (name "/O_IN_4") (class "Default")
      (node (ref "H8") (pin "3") (pinfunction "3_3") (pintype "passive"))
      (node (ref "R16") (pin "2") (pinfunction "2_2") (pintype "passive"))
      (node (ref "RN2") (pin "6") (pinfunction "6_6") (pintype "passive"))
      (node (ref "U6") (pin "6") (pinfunction "A3_6") (pintype "passive"))
    )
    (net (code "53") (name "/O_IN_5") (class "Default")
      (node (ref "H10") (pin "3") (pinfunction "3_3") (pintype "passive"))
      (node (ref "R17") (pin "2") (pinfunction "2_2") (pintype "passive"))
      (node (ref "RN2") (pin "7") (pinfunction "7_7") (pintype "passive"))
      (node (ref "U6") (pin "5") (pinfunction "A2_5") (pintype "passive"))
    )
    (net (code "54") (name "/O_IN_6") (class "Default")
      (node (ref "HD6") (pin "1") (pinfunction "1_1") (pintype "passive"))
      (node (ref "R20") (pin "2") (pinfunction "2_2") (pintype "passive"))
      (node (ref "RN2") (pin "8") (pinfunction "8_8") (pintype "passive"))
      (node (ref "U6") (pin "4") (pinfunction "A1_4") (pintype "passive"))
    )
    (net (code "55") (name "/O_IN_7") (class "Default")
      (node (ref "RN2") (pin "9") (pinfunction "9_9") (pintype "passive"))
      (node (ref "U6") (pin "3") (pinfunction "A0_3") (pintype "passive"))
    )
    (net (code "56") (name "/P17") (class "Default")
      (node (ref "RN1") (pin "3") (pinfunction "3_3") (pintype "passive"))
      (node (ref "U1") (pin "26") (pinfunction "26_26") (pintype "passive"))
      (node (ref "U4") (pin "20") (pinfunction "B1_20") (pintype "passive"))
    )
    (net (code "57") (name "/P19") (class "Default")
      (node (ref "RN1") (pin "5") (pinfunction "5_5") (pintype "passive"))
      (node (ref "U1") (pin "25") (pinfunction "25_25") (pintype "passive"))
      (node (ref "U4") (pin "18") (pinfunction "B3_18") (pintype "passive"))
    )
    (net (code "58") (name "/P21") (class "Default")
      (node (ref "RN1") (pin "7") (pinfunction "7_7") (pintype "passive"))
      (node (ref "U1") (pin "24") (pinfunction "24_24") (pintype "passive"))
      (node (ref "U4") (pin "16") (pinfunction "B5_16") (pintype "passive"))
    )
    (net (code "59") (name "/P33") (class "Default")
      (node (ref "RN1") (pin "9") (pinfunction "9_9") (pintype "passive"))
      (node (ref "U1") (pin "23") (pinfunction "23_23") (pintype "passive"))
      (node (ref "U4") (pin "14") (pinfunction "B7_14") (pintype "passive"))
    )
    (net (code "60") (name "/P35") (class "Default")
      (node (ref "U1") (pin "67") (pinfunction "67_67") (pintype "passive"))
    )
    (net (code "61") (name "/P36") (class "Default")
      (node (ref "U1") (pin "66") (pinfunction "66_66") (pintype "passive"))
    )
    (net (code "62") (name "/P38") (class "Default")
      (node (ref "U1") (pin "68") (pinfunction "68_68") (pintype "passive"))
    )
    (net (code "63") (name "/P40") (class "Default")
      (node (ref "U1") (pin "65") (pinfunction "65_65") (pintype "passive"))
    )
    (net (code "64") (name "/P41") (class "Default")
      (node (ref "U1") (pin "69") (pinfunction "69_69") (pintype "passive"))
    )
    (net (code "65") (name "/P42") (class "Default")
      (node (ref "U1") (pin "64") (pinfunction "64_64") (pintype "passive"))
    )
    (net (code "66") (name "/P47") (class "Default")
      (node (ref "U1") (pin "70") (pinfunction "70_70") (pintype "passive"))
    )
    (net (code "67") (name "/P48") (class "Default")
      (node (ref "U1") (pin "63") (pinfunction "63_63") (pintype "passive"))
    )
    (net (code "68") (name "/PA0") (class "Default")
      (node (ref "U1") (pin "38") (pinfunction "38_38") (pintype "passive"))
    )
    (net (code "69") (name "/PA1") (class "Default")
      (node (ref "U1") (pin "8") (pinfunction "8_8") (pintype "passive"))
    )
    (net (code "70") (name "/PA2") (class "Default")
      (node (ref "H7") (pin "1") (pinfunction "1_1") (pintype "passive"))
      (node (ref "U1") (pin "37") (pinfunction "37_37") (pintype "passive"))
    )
    (net (code "71") (name "/PA3") (class "Default")
      (node (ref "U1") (pin "9") (pinfunction "9_9") (pintype "passive"))
    )
    (net (code "72") (name "/PA4") (class "Default")
      (node (ref "U1") (pin "36") (pinfunction "36_36") (pintype "passive"))
    )
    (net (code "73") (name "/PA5") (class "Default")
      (node (ref "U1") (pin "10") (pinfunction "10_10") (pintype "passive"))
    )
    (net (code "74") (name "/PA6") (class "Default")
      (node (ref "U1") (pin "35") (pinfunction "35_35") (pintype "passive"))
    )
    (net (code "75") (name "/PA7") (class "Default")
      (node (ref "U1") (pin "11") (pinfunction "11_11") (pintype "passive"))
    )
    (net (code "76") (name "/PA8") (class "Default")
      (node (ref "U1") (pin "83") (pinfunction "83_83") (pintype "passive"))
    )
    (net (code "77") (name "/PA9") (class "Default")
      (node (ref "U1") (pin "49") (pinfunction "49_49") (pintype "passive"))
    )
    (net (code "78") (name "/PA10") (class "Default")
      (node (ref "U1") (pin "84") (pinfunction "84_84") (pintype "passive"))
    )
    (net (code "79") (name "/PA11") (class "Default")
      (node (ref "U1") (pin "48") (pinfunction "48_48") (pintype "passive"))
    )
    (net (code "80") (name "/PA12") (class "Default")
      (node (ref "U1") (pin "85") (pinfunction "85_85") (pintype "passive"))
    )
    (net (code "81") (name "/PA15") (class "Default")
      (node (ref "U1") (pin "47") (pinfunction "47_47") (pintype "passive"))
    )
    (net (code "82") (name "/PB0") (class "Default")
      (node (ref "U1") (pin "33") (pinfunction "33_33") (pintype "passive"))
    )
    (net (code "83") (name "/PB1") (class "Default")
      (node (ref "U1") (pin "13") (pinfunction "13_13") (pintype "passive"))
    )
    (net (code "84") (name "/PB2") (class "Default")
      (node (ref "U1") (pin "32") (pinfunction "32_32") (pintype "passive"))
    )
    (net (code "85") (name "/PB3") (class "Default")
      (node (ref "U1") (pin "2") (pinfunction "2_2") (pintype "passive"))
    )
    (net (code "86") (name "/PB4") (class "Default")
      (node (ref "U1") (pin "43") (pinfunction "43_43") (pintype "passive"))
    )
    (net (code "87") (name "/PB5") (class "Default")
      (node (ref "U1") (pin "3") (pinfunction "3_3") (pintype "passive"))
    )
    (net (code "88") (name "/PB6") (class "Default")
      (node (ref "U1") (pin "42") (pinfunction "42_42") (pintype "passive"))
    )
    (net (code "89") (name "/PB10") (class "Default")
      (node (ref "H12") (pin "2") (pinfunction "2_2") (pintype "passive"))
      (node (ref "U1") (pin "55") (pinfunction "55_55") (pintype "passive"))
    )
    (net (code "90") (name "/PB11") (class "Default")
      (node (ref "H12") (pin "1") (pinfunction "1_1") (pintype "passive"))
      (node (ref "U1") (pin "78") (pinfunction "78_78") (pintype "passive"))
    )
    (net (code "91") (name "/PB12") (class "Default")
      (node (ref "U1") (pin "54") (pinfunction "54_54") (pintype "passive"))
    )
    (net (code "92") (name "/PB13") (class "Default")
      (node (ref "U1") (pin "79") (pinfunction "79_79") (pintype "passive"))
    )
    (net (code "93") (name "/PB14") (class "Default")
      (node (ref "U1") (pin "53") (pinfunction "53_53") (pintype "passive"))
    )
    (net (code "94") (name "/PB15") (class "Default")
      (node (ref "U1") (pin "80") (pinfunction "80_80") (pintype "passive"))
    )
    (net (code "95") (name "/PC3") (class "Default")
      (node (ref "U1") (pin "39") (pinfunction "39_39") (pintype "passive"))
    )
    (net (code "96") (name "/PC4") (class "Default")
      (node (ref "U1") (pin "34") (pinfunction "34_34") (pintype "passive"))
    )
    (net (code "97") (name "/PC6") (class "Default")
      (node (ref "U1") (pin "81") (pinfunction "81_81") (pintype "passive"))
    )
    (net (code "98") (name "/PC7") (class "Default")
      (node (ref "U1") (pin "51") (pinfunction "51_51") (pintype "passive"))
    )
    (net (code "99") (name "/PC8") (class "Default")
      (node (ref "U1") (pin "82") (pinfunction "82_82") (pintype "passive"))
    )
    (net (code "100") (name "/PC9") (class "Default")
      (node (ref "U1") (pin "50") (pinfunction "50_50") (pintype "passive"))
    )
    (net (code "101") (name "/PC10") (class "Default")
      (node (ref "U1") (pin "86") (pinfunction "86_86") (pintype "passive"))
    )
    (net (code "102") (name "/PC11") (class "Default")
      (node (ref "U1") (pin "46") (pinfunction "46_46") (pintype "passive"))
    )
    (net (code "103") (name "/PC12") (class "Default")
      (node (ref "U1") (pin "87") (pinfunction "87_87") (pintype "passive"))
    )
    (net (code "104") (name "/PD0") (class "Default")
      (node (ref "U1") (pin "56") (pinfunction "56_56") (pintype "passive"))
    )
    (net (code "105") (name "/PD1") (class "Default")
      (node (ref "U1") (pin "77") (pinfunction "77_77") (pintype "passive"))
    )
    (net (code "106") (name "/PD2") (class "Default")
      (node (ref "U1") (pin "57") (pinfunction "57_57") (pintype "passive"))
    )
    (net (code "107") (name "/PD3") (class "Default")
      (node (ref "U1") (pin "76") (pinfunction "76_76") (pintype "passive"))
    )
    (net (code "108") (name "/PE0") (class "Default")
      (node (ref "U1") (pin "5") (pinfunction "5_5") (pintype "passive"))
    )
    (net (code "109") (name "/PE1") (class "Default")
      (node (ref "U1") (pin "40") (pinfunction "40_40") (pintype "passive"))
    )
    (net (code "111") (name "3V3") (class "Default")
      (node (ref "C19") (pin "1") (pinfunction "1_1") (pintype "passive"))
      (node (ref "C25") (pin "2") (pinfunction "2_2") (pintype "passive"))
      (node (ref "C3") (pin "1") (pinfunction "1_1") (pintype "passive"))
      (node (ref "C4") (pin "1") (pinfunction "1_1") (pintype "passive"))
      (node (ref "IC1") (pin "2") (pinfunction "OUT_2") (pintype "passive"))
      (node (ref "IC1") (pin "4") (pinfunction "PAD_4") (pintype "passive"))
      (node (ref "R8") (pin "1") (pinfunction "1_1") (pintype "passive"))
      (node (ref "U4") (pin "23") (pinfunction "VCCB_23") (pintype "passive"))
      (node (ref "U4") (pin "24") (pinfunction "VCC(B)_24") (pintype "passive"))
      (node (ref "U5") (pin "23") (pinfunction "VCCB_23") (pintype "passive"))
      (node (ref "U5") (pin "24") (pinfunction "VCC(B)_24") (pintype "passive"))
      (node (ref "U6") (pin "23") (pinfunction "VCCB_23") (pintype "passive"))
      (node (ref "U6") (pin "24") (pinfunction "VCC(B)_24") (pintype "passive"))
    )
    (net (code "112") (name "3V3_Board") (class "Default")
      (node (ref "C14") (pin "2") (pinfunction "2_2") (pintype "passive"))
      (node (ref "IC2") (pin "8") (pinfunction "VCC_8") (pintype "power_in"))
      (node (ref "R15") (pin "1") (pinfunction "1_1") (pintype "passive"))
      (node (ref "R18") (pin "2") (pinfunction "2_2") (pintype "passive"))
      (node (ref "R19") (pin "1") (pinfunction "1_1") (pintype "passive"))
      (node (ref "U1") (pin "44") (pinfunction "44_44") (pintype "passive"))
      (node (ref "U1") (pin "7") (pinfunction "7_7") (pintype "passive"))
    )
    (net (code "113") (name "5V") (class "Default")
      (node (ref "C1") (pin "1") (pinfunction "1_1") (pintype "passive"))
      (node (ref "C2") (pin "1") (pinfunction "1_1") (pintype "passive"))
      (node (ref "C24") (pin "1") (pinfunction "1_1") (pintype "passive"))
      (node (ref "C26") (pin "2") (pinfunction "2_2") (pintype "passive"))
      (node (ref "H1") (pin "2") (pinfunction "2_2") (pintype "passive"))
      (node (ref "H10") (pin "2") (pinfunction "2_2") (pintype "passive"))
      (node (ref "H11") (pin "1") (pinfunction "1_1") (pintype "passive"))
      (node (ref "H2") (pin "2") (pinfunction "2_2") (pintype "passive"))
      (node (ref "H3") (pin "2") (pinfunction "2_2") (pintype "passive"))
      (node (ref "H4") (pin "1") (pinfunction "1_1") (pintype "passive"))
      (node (ref "H5") (pin "2") (pinfunction "2_2") (pintype "passive"))
      (node (ref "H6") (pin "1") (pinfunction "1_1") (pintype "passive"))
      (node (ref "H7") (pin "2") (pinfunction "2_2") (pintype "passive"))
      (node (ref "H8") (pin "2") (pinfunction "2_2") (pintype "passive"))
      (node (ref "H9") (pin "1") (pinfunction "1_1") (pintype "passive"))
      (node (ref "HD1") (pin "2") (pinfunction "2_2") (pintype "passive"))
      (node (ref "HD6") (pin "2") (pinfunction "2_2") (pintype "passive"))
      (node (ref "IC1") (pin "3") (pinfunction "IN_3") (pintype "passive"))
      (node (ref "R21") (pin "2") (pinfunction "2_2") (pintype "passive"))
      (node (ref "R22") (pin "2") (pinfunction "2_2") (pintype "passive"))
      (node (ref "R23") (pin "2") (pinfunction "2_2") (pintype "passive"))
      (node (ref "R24") (pin "2") (pinfunction "2_2") (pintype "passive"))
      (node (ref "R25") (pin "2") (pinfunction "2_2") (pintype "passive"))
      (node (ref "R26") (pin "2") (pinfunction "2_2") (pintype "passive"))
      (node (ref "R27") (pin "2") (pinfunction "2_2") (pintype "passive"))
      (node (ref "R28") (pin "2") (pinfunction "2_2") (pintype "passive"))
      (node (ref "R7") (pin "1") (pinfunction "1_1") (pintype "passive"))
      (node (ref "U1") (pin "88") (pinfunction "88_88") (pintype "passive"))
      (node (ref "U2") (pin "14") (pinfunction "VCC_14") (pintype "passive"))
      (node (ref "U3") (pin "14") (pinfunction "VCC_14") (pintype "passive"))
      (node (ref "U4") (pin "1") (pinfunction "VCC(A)_1") (pintype "passive"))
      (node (ref "U5") (pin "1") (pinfunction "VCC(A)_1") (pintype "passive"))
      (node (ref "U5") (pin "2") (pinfunction "DIR_2") (pintype "passive"))
      (node (ref "U6") (pin "1") (pinfunction "VCC(A)_1") (pintype "passive"))
      (node (ref "U6") (pin "2") (pinfunction "DIR_2") (pintype "passive"))
    )
    (net (code "114") (name "GND") (class "Default")
      (node (ref "C1") (pin "2") (pinfunction "2_2") (pintype "passive"))
      (node (ref "C10") (pin "1") (pinfunction "1_1") (pintype "passive"))
      (node (ref "C11") (pin "1") (pinfunction "1_1") (pintype "passive"))
      (node (ref "C12") (pin "1") (pinfunction "1_1") (pintype "passive"))
      (node (ref "C13") (pin "2") (pinfunction "2_2") (pintype "passive"))
      (node (ref "C14") (pin "1") (pinfunction "1_1") (pintype "passive"))
      (node (ref "C15") (pin "1") (pinfunction "1_1") (pintype "passive"))
      (node (ref "C16") (pin "1") (pinfunction "1_1") (pintype "passive"))
      (node (ref "C17") (pin "1") (pinfunction "1_1") (pintype "passive"))
      (node (ref "C18") (pin "1") (pinfunction "1_1") (pintype "passive"))
      (node (ref "C19") (pin "2") (pinfunction "2_2") (pintype "passive"))
      (node (ref "C2") (pin "2") (pinfunction "2_2") (pintype "passive"))
      (node (ref "C20") (pin "1") (pinfunction "1_1") (pintype "passive"))
      (node (ref "C21") (pin "1") (pinfunction "1_1") (pintype "passive"))
      (node (ref "C22") (pin "1") (pinfunction "1_1") (pintype "passive"))
      (node (ref "C23") (pin "1") (pinfunction "1_1") (pintype "passive"))
      (node (ref "C24") (pin "2") (pinfunction "2_2") (pintype "passive"))
      (node (ref "C25") (pin "1") (pinfunction "1_1") (pintype "passive"))
      (node (ref "C26") (pin "1") (pinfunction "1_1") (pintype "passive"))
      (node (ref "C3") (pin "2") (pinfunction "2_2") (pintype "passive"))
      (node (ref "C4") (pin "2") (pinfunction "2_2") (pintype "passive"))
      (node (ref "C5") (pin "1") (pinfunction "1_1") (pintype "passive"))
      (node (ref "C6") (pin "1") (pinfunction "1_1") (pintype "passive"))
      (node (ref "C7") (pin "1") (pinfunction "1_1") (pintype "passive"))
      (node (ref "C8") (pin "1") (pinfunction "1_1") (pintype "passive"))
      (node (ref "C9") (pin "1") (pinfunction "1_1") (pintype "passive"))
      (node (ref "D1") (pin "2") (pinfunction "K_2") (pintype "passive"))
      (node (ref "D2") (pin "2") (pinfunction "K_2") (pintype "passive"))
      (node (ref "D3") (pin "2") (pinfunction "K_2") (pintype "passive"))
      (node (ref "D4") (pin "2") (pinfunction "K_2") (pintype "passive"))
      (node (ref "D5") (pin "2") (pinfunction "K_2") (pintype "passive"))
      (node (ref "D6") (pin "2") (pinfunction "K_2") (pintype "passive"))
      (node (ref "D7") (pin "2") (pinfunction "K_2") (pintype "passive"))
      (node (ref "D8") (pin "2") (pinfunction "K_2") (pintype "passive"))
      (node (ref "D9") (pin "2") (pinfunction "K_2") (pintype "passive"))
      (node (ref "H1") (pin "1") (pinfunction "1_1") (pintype "passive"))
      (node (ref "H10") (pin "1") (pinfunction "1_1") (pintype "passive"))
      (node (ref "H11") (pin "4") (pinfunction "4_4") (pintype "passive"))
      (node (ref "H12") (pin "3") (pinfunction "3_3") (pintype "passive"))
      (node (ref "H2") (pin "1") (pinfunction "1_1") (pintype "passive"))
      (node (ref "H3") (pin "1") (pinfunction "1_1") (pintype "passive"))
      (node (ref "H4") (pin "4") (pinfunction "4_4") (pintype "passive"))
      (node (ref "H5") (pin "1") (pinfunction "1_1") (pintype "passive"))
      (node (ref "H6") (pin "4") (pinfunction "4_4") (pintype "passive"))
      (node (ref "H7") (pin "3") (pinfunction "3_3") (pintype "passive"))
      (node (ref "H8") (pin "1") (pinfunction "1_1") (pintype "passive"))
      (node (ref "H9") (pin "4") (pinfunction "4_4") (pintype "passive"))
      (node (ref "HD1") (pin "1") (pinfunction "1_1") (pintype "passive"))
      (node (ref "IC1") (pin "1") (pinfunction "ADJ/G_1") (pintype "passive"))
      (node (ref "IC2") (pin "1") (pinfunction "A0_1") (pintype "passive"))
      (node (ref "IC2") (pin "2") (pinfunction "A1_2") (pintype "passive"))
      (node (ref "IC2") (pin "3") (pinfunction "A2_3") (pintype "passive"))
      (node (ref "IC2") (pin "4") (pinfunction "GND_4") (pintype "power_in"))
      (node (ref "IC2") (pin "7") (pinfunction "WP_7") (pintype "passive"))
      (node (ref "R10") (pin "2") (pinfunction "2_2") (pintype "passive"))
      (node (ref "R11") (pin "2") (pinfunction "2_2") (pintype "passive"))
      (node (ref "R12") (pin "2") (pinfunction "2_2") (pintype "passive"))
      (node (ref "R14") (pin "2") (pinfunction "2_2") (pintype "passive"))
      (node (ref "R2") (pin "2") (pinfunction "2_2") (pintype "passive"))
      (node (ref "R3") (pin "2") (pinfunction "2_2") (pintype "passive"))
      (node (ref "R4") (pin "1") (pinfunction "1_1") (pintype "passive"))
      (node (ref "R6") (pin "2") (pinfunction "2_2") (pintype "passive"))
      (node (ref "RN1") (pin "1") (pinfunction "1_1") (pintype "passive"))
      (node (ref "RN2") (pin "1") (pinfunction "1_1") (pintype "passive"))
      (node (ref "S1") (pin "1") (pinfunction "1_1") (pintype "passive"))
      (node (ref "U1") (pin "1") (pinfunction "1_1") (pintype "passive"))
      (node (ref "U1") (pin "14") (pinfunction "14_14") (pintype "passive"))
      (node (ref "U1") (pin "31") (pinfunction "31_31") (pintype "passive"))
      (node (ref "U1") (pin "45") (pinfunction "45_45") (pintype "passive"))
      (node (ref "U1") (pin "58") (pinfunction "58_58") (pintype "passive"))
      (node (ref "U1") (pin "75") (pinfunction "75_75") (pintype "passive"))
      (node (ref "U2") (pin "7") (pinfunction "GND_7") (pintype "passive"))
      (node (ref "U3") (pin "7") (pinfunction "GND_7") (pintype "passive"))
      (node (ref "U4") (pin "11") (pinfunction "GND_11") (pintype "passive"))
      (node (ref "U4") (pin "12") (pinfunction "GND_12") (pintype "passive"))
      (node (ref "U4") (pin "13") (pinfunction "GND_13") (pintype "passive"))
      (node (ref "U4") (pin "2") (pinfunction "DIR_2") (pintype "passive"))
      (node (ref "U4") (pin "22") (pinfunction "~{OE}_22") (pintype "passive"))
      (node (ref "U5") (pin "11") (pinfunction "GND_11") (pintype "passive"))
      (node (ref "U5") (pin "12") (pinfunction "GND_12") (pintype "passive"))
      (node (ref "U5") (pin "13") (pinfunction "GND_13") (pintype "passive"))
      (node (ref "U5") (pin "22") (pinfunction "~{OE}_22") (pintype "passive"))
      (node (ref "U6") (pin "11") (pinfunction "GND_11") (pintype "passive"))
      (node (ref "U6") (pin "12") (pinfunction "GND_12") (pintype "passive"))
      (node (ref "U6") (pin "13") (pinfunction "GND_13") (pintype "passive"))
      (node (ref "U6") (pin "22") (pinfunction "~{OE}_22") (pintype "passive"))
    )
    (net (code "115") (name "Net-(D1-A)") (class "Default")
      (node (ref "D1") (pin "1") (pinfunction "A_1") (pintype "passive"))
      (node (ref "R1") (pin "1") (pinfunction "1_1") (pintype "passive"))
    )
    (net (code "116") (name "Net-(D2-A)") (class "Default")
      (node (ref "D2") (pin "1") (pinfunction "A_1") (pintype "passive"))
      (node (ref "R5") (pin "1") (pinfunction "1_1") (pintype "passive"))
    )
    (net (code "117") (name "Net-(D3-A)") (class "Default")
      (node (ref "D3") (pin "1") (pinfunction "A_1") (pintype "passive"))
      (node (ref "R7") (pin "2") (pinfunction "2_2") (pintype "passive"))
    )
    (net (code "118") (name "Net-(D4-A)") (class "Default")
      (node (ref "D4") (pin "1") (pinfunction "A_1") (pintype "passive"))
      (node (ref "R8") (pin "2") (pinfunction "2_2") (pintype "passive"))
    )
    (net (code "119") (name "Net-(D5-A)") (class "Default")
      (node (ref "D5") (pin "1") (pinfunction "A_1") (pintype "passive"))
      (node (ref "R9") (pin "1") (pinfunction "1_1") (pintype "passive"))
    )
    (net (code "120") (name "Net-(D6-A)") (class "Default")
      (node (ref "D6") (pin "1") (pinfunction "A_1") (pintype "passive"))
      (node (ref "R13") (pin "1") (pinfunction "1_1") (pintype "passive"))
    )
    (net (code "121") (name "Net-(D7-A)") (class "Default")
      (node (ref "D7") (pin "1") (pinfunction "A_1") (pintype "passive"))
      (node (ref "R16") (pin "1") (pinfunction "1_1") (pintype "passive"))
    )
    (net (code "122") (name "Net-(D8-A)") (class "Default")
      (node (ref "D8") (pin "1") (pinfunction "A_1") (pintype "passive"))
      (node (ref "R17") (pin "1") (pinfunction "1_1") (pintype "passive"))
    )
    (net (code "123") (name "Net-(D9-A)") (class "Default")
      (node (ref "D9") (pin "1") (pinfunction "A_1") (pintype "passive"))
      (node (ref "R20") (pin "1") (pinfunction "1_1") (pintype "passive"))
    )
    (net (code "124") (name "unconnected-(U1-Pad12)") (class "Default")
      (node (ref "U1") (pin "12") (pinfunction "12_12") (pintype "passive"))
    )
    (net (code "125") (name "unconnected-(U1-Pad52)") (class "Default")
      (node (ref "U1") (pin "52") (pinfunction "52_52") (pintype "passive+no_connect"))
    )
    (net (code "126") (name "unconnected-(U2-7-Pad8)") (class "Default")
      (node (ref "U2") (pin "8") (pinfunction "7_8") (pintype "passive"))
    )
    (net (code "127") (name "unconnected-(U2-8-Pad9)") (class "Default")
      (node (ref "U2") (pin "9") (pinfunction "8_9") (pintype "passive"))
    )
    (net (code "128") (name "unconnected-(U2-Pad5)") (class "Default")
      (node (ref "U2") (pin "5") (pintype "passive"))
    )
    (net (code "129") (name "unconnected-(U2-Pad6)") (class "Default")
      (node (ref "U2") (pin "6") (pintype "passive"))
    )
    (net (code "130") (name "unconnected-(U3-7-Pad8)") (class "Default")
      (node (ref "U3") (pin "8") (pinfunction "7_8") (pintype "passive"))
    )
    (net (code "131") (name "unconnected-(U3-8-Pad9)") (class "Default")
      (node (ref "U3") (pin "9") (pinfunction "8_9") (pintype "passive"))
    )
    (net (code "132") (name "unconnected-(U3-Pad5)") (class "Default")
      (node (ref "U3") (pin "5") (pintype "passive"))
    )
    (net (code "133") (name "unconnected-(U3-Pad6)") (class "Default")
      (node (ref "U3") (pin "6") (pintype "passive"))
    )
    (net (code "134") (name "unconnected-(U6-B0-Pad21)") (class "Default")
      (node (ref "U6") (pin "21") (pinfunction "B0_21") (pintype "passive"))
    )
  )
)
